# MySens-GWeasySensRS485-002.net
KiCad netlist of a schematic drawn in EAGLE
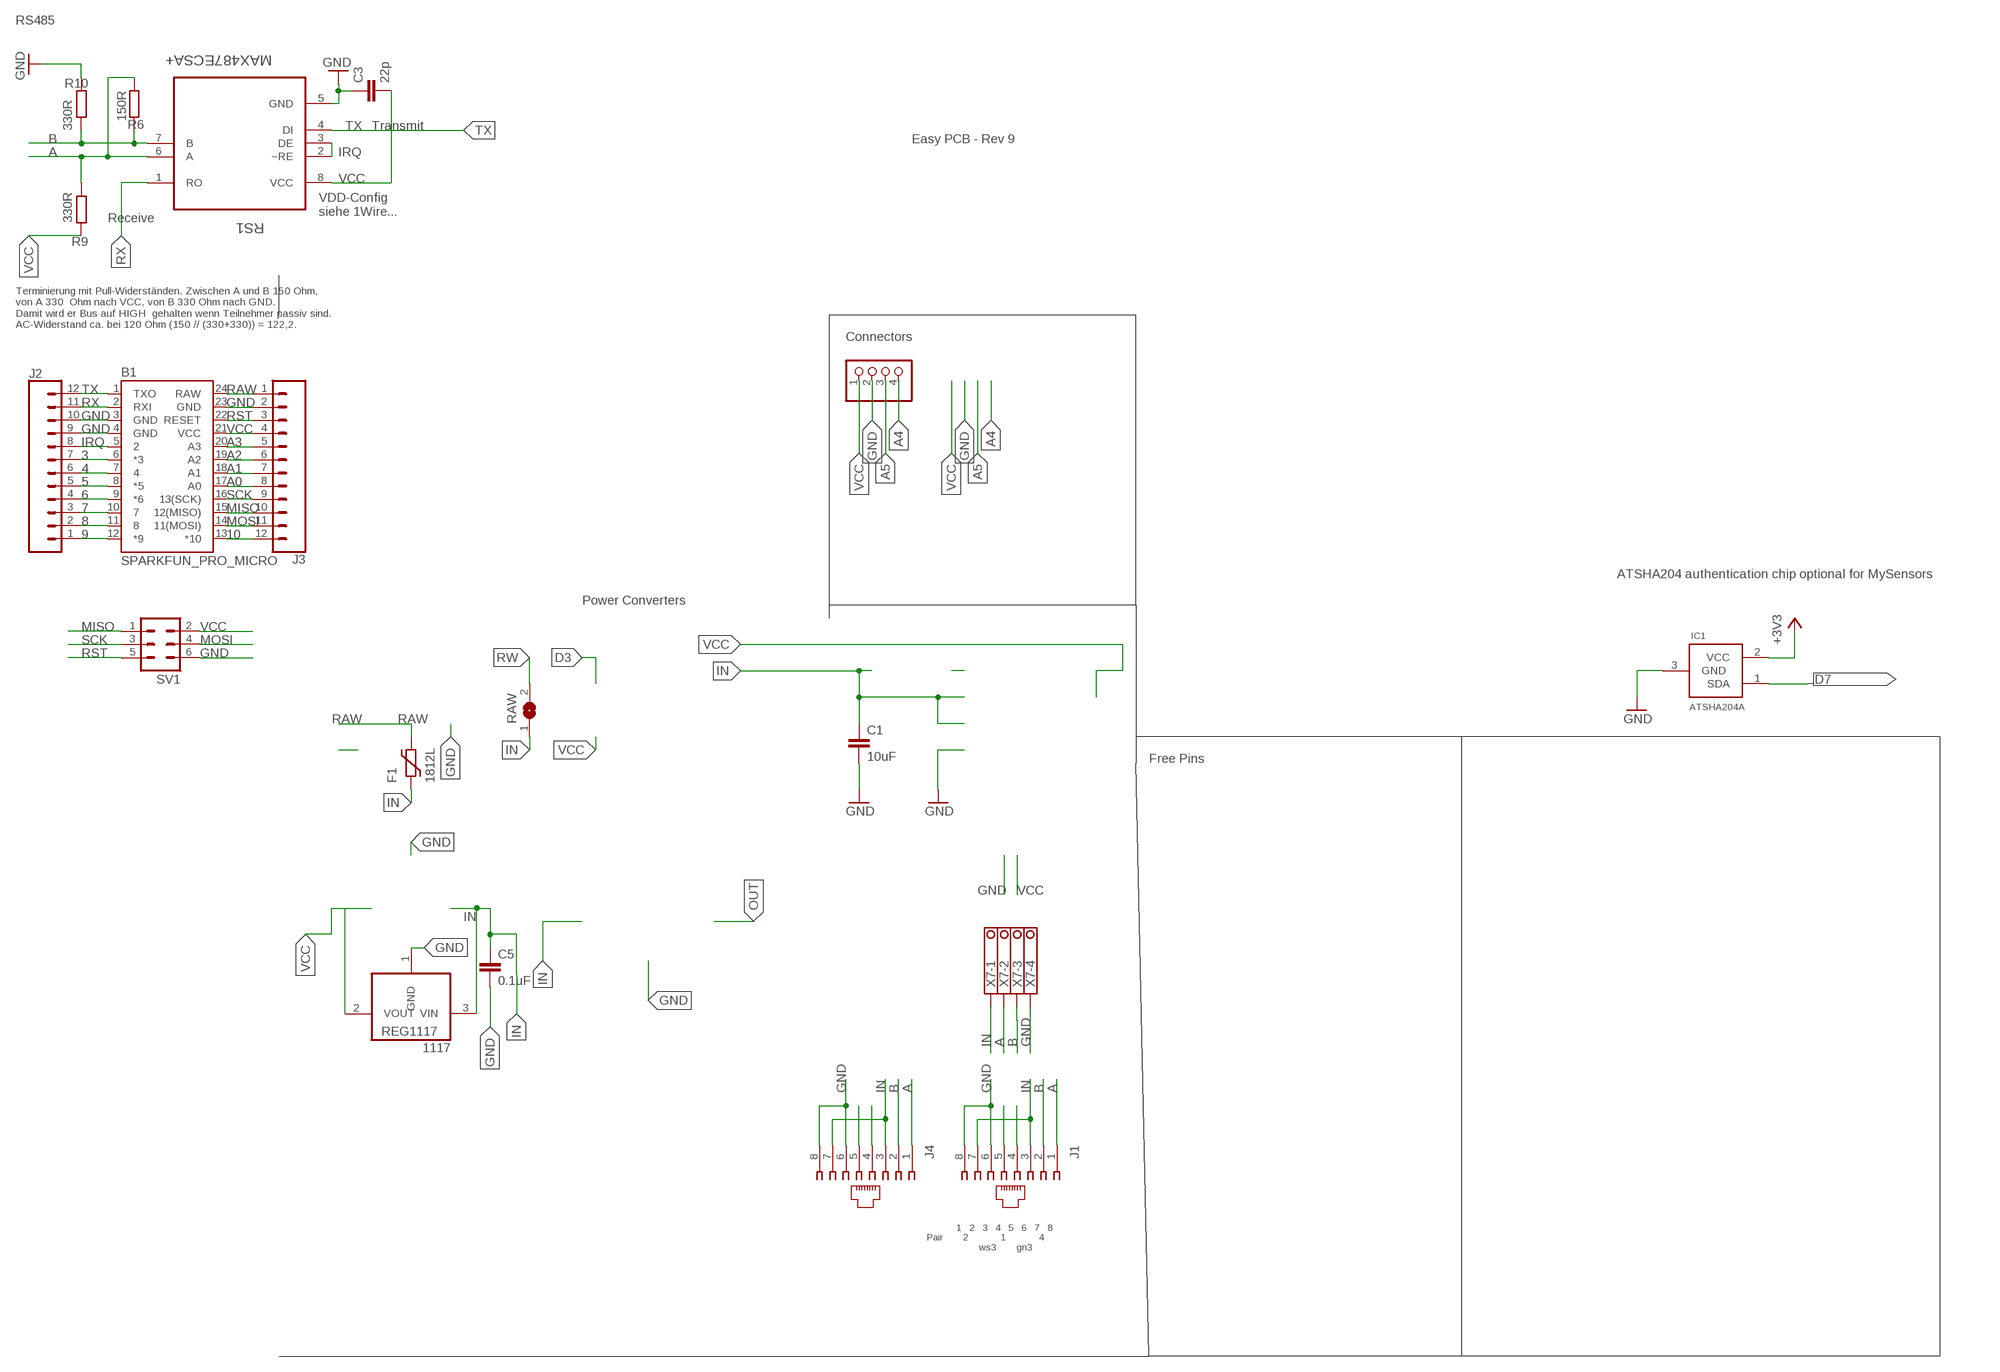
[diagram p0: schematic, sheet 1]

(export (version "E")
  (design (tool "Eeschema 10.0.6"))
  (components
    (comp (ref "1117")
      (value "REG1117")
      (footprint "eagle-import:SOT223")
      (libsource (lib "eagle-import") (part "REG1117"))
    )
    (comp (ref "B1")
      (value "SPARKFUN_PRO_MICRO")
      (footprint "eagle-import:SPARKFUN_PRO_MICRO")
      (libsource (lib "eagle-import") (part "SPARKFUN_PRO_MICRO"))
    )
    (comp (ref "C1")
      (value "10uF")
      (footprint "eagle-import:0805")
      (libsource (lib "eagle-import") (part "CAP0805"))
    )
    (comp (ref "C3")
      (value "22p")
      (footprint "eagle-import:C0805")
      (libsource (lib "eagle-import") (part "C-EUC0805"))
    )
    (comp (ref "C5")
      (value "0.1uF")
      (footprint "eagle-import:C1206")
      (libsource (lib "eagle-import") (part "C-EUC1206"))
    )
    (comp (ref "F1")
      (value "1812L")
      (footprint "eagle-import:1812L")
      (libsource (lib "eagle-import") (part "1812L"))
    )
    (comp (ref "IC1")
      (value "ATSHA204A")
      (footprint "eagle-import:SOT23")
      (libsource (lib "eagle-import") (part "ATSHA204A"))
    )
    (comp (ref "J1")
      (value "215878-2")
      (footprint "eagle-import:215878-2")
      (libsource (lib "eagle-import") (part "215878-2"))
    )
    (comp (ref "J2")
      (value "CONN_12")
      (footprint "eagle-import:1X12")
      (libsource (lib "eagle-import") (part "CONN_12"))
    )
    (comp (ref "J3")
      (value "CONN_12")
      (footprint "eagle-import:1X12")
      (libsource (lib "eagle-import") (part "CONN_12"))
    )
    (comp (ref "J4")
      (value "215878-2")
      (footprint "eagle-import:215878-2")
      (libsource (lib "eagle-import") (part "215878-2"))
    )
    (comp (ref "JP10")
      (value "PINHD-1X04_2.54-S")
      (footprint "eagle-import:1X04-S")
      (libsource (lib "eagle-import") (part "PINHD-1X04_2.54-S"))
    )
    (comp (ref "R6")
      (value "150R")
      (footprint "eagle-import:R0805")
      (libsource (lib "eagle-import") (part "R-EU_R0805"))
    )
    (comp (ref "R9")
      (value "330R")
      (footprint "eagle-import:R0805")
      (libsource (lib "eagle-import") (part "R-EU_R0805"))
    )
    (comp (ref "R10")
      (value "330R")
      (footprint "eagle-import:R0805")
      (libsource (lib "eagle-import") (part "R-EU_R0805"))
    )
    (comp (ref "RAW") (value "SJ") (footprint "eagle-import:SJ") (libsource (lib "eagle-import") (part "SJ")))
    (comp (ref "RS1")
      (value "MAX487ECSA+")
      (footprint "eagle-import:SOIC127P600X175-8N")
      (libsource (lib "eagle-import") (part "MAX487ECSA+"))
    )
    (comp (ref "SV1")
      (value "MA03-2")
      (footprint "eagle-import:MA03-2")
      (libsource (lib "eagle-import") (part "MA03-2"))
    )
    (comp (ref "X7")
      (value "1751264")
      (footprint "eagle-import:1751264")
      (libsource (lib "eagle-import") (part "1751264"))
    )
  )
  (nets
    (net (code "1") (name "+3V3") (class "Default")
      (node (ref "IC1") (pin "2") (pinfunction "VCC_2") (pintype "bidirectional"))
    )
    (net (code "2") (name "/3") (class "Default")
      (node (ref "B1") (pin "6") (pinfunction "*3_6") (pintype "bidirectional"))
      (node (ref "J2") (pin "7") (pinfunction "7_7") (pintype "passive"))
    )
    (net (code "3") (name "/4") (class "Default")
      (node (ref "B1") (pin "7") (pinfunction "4_7") (pintype "bidirectional"))
      (node (ref "J2") (pin "6") (pinfunction "6_6") (pintype "passive"))
    )
    (net (code "4") (name "/5") (class "Default")
      (node (ref "B1") (pin "8") (pinfunction "*5_8") (pintype "bidirectional"))
      (node (ref "J2") (pin "5") (pinfunction "5_5") (pintype "passive"))
    )
    (net (code "5") (name "/6") (class "Default")
      (node (ref "B1") (pin "9") (pinfunction "*6_9") (pintype "bidirectional"))
      (node (ref "J2") (pin "4") (pinfunction "4_4") (pintype "passive"))
    )
    (net (code "6") (name "/7") (class "Default")
      (node (ref "B1") (pin "10") (pinfunction "7_10") (pintype "bidirectional"))
      (node (ref "J2") (pin "3") (pinfunction "3_3") (pintype "passive"))
    )
    (net (code "7") (name "/8") (class "Default")
      (node (ref "B1") (pin "11") (pinfunction "8_11") (pintype "bidirectional"))
      (node (ref "J2") (pin "2") (pinfunction "2_2") (pintype "passive"))
    )
    (net (code "8") (name "/9") (class "Default")
      (node (ref "B1") (pin "12") (pinfunction "*9_12") (pintype "bidirectional"))
      (node (ref "J2") (pin "1") (pinfunction "1_1") (pintype "passive"))
    )
    (net (code "9") (name "/10") (class "Default")
      (node (ref "B1") (pin "13") (pinfunction "*10_13") (pintype "bidirectional"))
      (node (ref "J3") (pin "12") (pinfunction "12_12") (pintype "passive"))
    )
    (net (code "10") (name "/A") (class "Default")
      (node (ref "J1") (pin "1") (pinfunction "1_1") (pintype "passive"))
      (node (ref "J4") (pin "1") (pinfunction "1_1") (pintype "passive"))
      (node (ref "R6") (pin "1") (pinfunction "1_1") (pintype "passive"))
      (node (ref "R9") (pin "2") (pinfunction "2_2") (pintype "passive"))
      (node (ref "RS1") (pin "6") (pinfunction "A_6") (pintype "bidirectional"))
      (node (ref "X7") (pin "2") (pinfunction "K_2") (pintype "passive"))
    )
    (net (code "11") (name "/A0") (class "Default")
      (node (ref "B1") (pin "17") (pinfunction "A0_17") (pintype "bidirectional"))
      (node (ref "J3") (pin "8") (pinfunction "8_8") (pintype "passive"))
    )
    (net (code "12") (name "/A1") (class "Default")
      (node (ref "B1") (pin "18") (pinfunction "A1_18") (pintype "bidirectional"))
      (node (ref "J3") (pin "7") (pinfunction "7_7") (pintype "passive"))
    )
    (net (code "13") (name "/A2") (class "Default")
      (node (ref "B1") (pin "19") (pinfunction "A2_19") (pintype "bidirectional"))
      (node (ref "J3") (pin "6") (pinfunction "6_6") (pintype "passive"))
    )
    (net (code "14") (name "/A3") (class "Default")
      (node (ref "B1") (pin "20") (pinfunction "A3_20") (pintype "bidirectional"))
      (node (ref "J3") (pin "5") (pinfunction "5_5") (pintype "passive"))
    )
    (net (code "15") (name "/B") (class "Default")
      (node (ref "J1") (pin "2") (pinfunction "2_2") (pintype "passive"))
      (node (ref "J4") (pin "2") (pinfunction "2_2") (pintype "passive"))
      (node (ref "R10") (pin "1") (pinfunction "1_1") (pintype "passive"))
      (node (ref "R6") (pin "2") (pinfunction "2_2") (pintype "passive"))
      (node (ref "RS1") (pin "7") (pinfunction "B_7") (pintype "bidirectional"))
      (node (ref "X7") (pin "3") (pinfunction "K_3") (pintype "passive"))
    )
    (net (code "16") (name "/D7") (class "Default")
      (node (ref "IC1") (pin "1") (pinfunction "SDA_1") (pintype "bidirectional"))
    )
    (net (code "17") (name "/IRQ") (class "Default")
      (node (ref "B1") (pin "5") (pinfunction "2_5") (pintype "bidirectional"))
      (node (ref "J2") (pin "8") (pinfunction "8_8") (pintype "passive"))
      (node (ref "RS1") (pin "2") (pinfunction "~{RE}_2") (pintype "input"))
      (node (ref "RS1") (pin "3") (pinfunction "DE_3") (pintype "input"))
    )
    (net (code "18") (name "/MISO") (class "Default")
      (node (ref "B1") (pin "15") (pinfunction "12(MISO)_15") (pintype "bidirectional"))
      (node (ref "J3") (pin "10") (pinfunction "10_10") (pintype "passive"))
      (node (ref "SV1") (pin "1") (pinfunction "1_1") (pintype "passive"))
    )
    (net (code "19") (name "/MOSI") (class "Default")
      (node (ref "B1") (pin "14") (pinfunction "11(MOSI)_14") (pintype "bidirectional"))
      (node (ref "J3") (pin "11") (pinfunction "11_11") (pintype "passive"))
      (node (ref "SV1") (pin "4") (pinfunction "4_4") (pintype "passive"))
    )
    (net (code "20") (name "/RAW") (class "Default")
      (node (ref "B1") (pin "24") (pinfunction "RAW_24") (pintype "power_in"))
      (node (ref "F1") (pin "P$2") (pinfunction "2_P$2") (pintype "passive"))
      (node (ref "J3") (pin "1") (pinfunction "1_1") (pintype "passive"))
    )
    (net (code "21") (name "/RST") (class "Default")
      (node (ref "B1") (pin "22") (pinfunction "RESET_22") (pintype "bidirectional"))
      (node (ref "J3") (pin "3") (pinfunction "3_3") (pintype "passive"))
      (node (ref "SV1") (pin "5") (pinfunction "5_5") (pintype "passive"))
    )
    (net (code "22") (name "/SCK") (class "Default")
      (node (ref "B1") (pin "16") (pinfunction "13(SCK)_16") (pintype "bidirectional"))
      (node (ref "J3") (pin "9") (pinfunction "9_9") (pintype "passive"))
      (node (ref "SV1") (pin "3") (pinfunction "3_3") (pintype "passive"))
    )
    (net (code "23") (name "A4") (class "Default")
      (node (ref "JP10") (pin "4") (pinfunction "4_4") (pintype "passive"))
    )
    (net (code "24") (name "A5") (class "Default")
      (node (ref "JP10") (pin "3") (pinfunction "3_3") (pintype "passive"))
    )
    (net (code "26") (name "GND") (class "Default")
      (node (ref "1117") (pin "1") (pinfunction "GND_1") (pintype "power_in"))
      (node (ref "B1") (pin "23") (pinfunction "GND_23") (pintype "power_in"))
      (node (ref "B1") (pin "3") (pinfunction "GND_3") (pintype "power_in"))
      (node (ref "B1") (pin "4") (pinfunction "GND_4") (pintype "power_in"))
      (node (ref "C1") (pin "2") (pinfunction "2_2") (pintype "passive"))
      (node (ref "C3") (pin "1") (pinfunction "1_1") (pintype "passive"))
      (node (ref "C5") (pin "2") (pinfunction "2_2") (pintype "passive"))
      (node (ref "IC1") (pin "3") (pinfunction "GND_3") (pintype "bidirectional"))
      (node (ref "J1") (pin "6") (pinfunction "6_6") (pintype "passive"))
      (node (ref "J1") (pin "8") (pinfunction "8_8") (pintype "passive"))
      (node (ref "J2") (pin "10") (pinfunction "10_10") (pintype "passive"))
      (node (ref "J2") (pin "9") (pinfunction "9_9") (pintype "passive"))
      (node (ref "J3") (pin "2") (pinfunction "2_2") (pintype "passive"))
      (node (ref "J4") (pin "6") (pinfunction "6_6") (pintype "passive"))
      (node (ref "J4") (pin "8") (pinfunction "8_8") (pintype "passive"))
      (node (ref "JP10") (pin "2") (pinfunction "2_2") (pintype "passive"))
      (node (ref "R10") (pin "2") (pinfunction "2_2") (pintype "passive"))
      (node (ref "RS1") (pin "5") (pinfunction "GND_5") (pintype "passive"))
      (node (ref "SV1") (pin "6") (pinfunction "6_6") (pintype "passive"))
      (node (ref "X7") (pin "4") (pinfunction "K_4") (pintype "passive"))
    )
    (net (code "27") (name "IN") (class "Default")
      (node (ref "1117") (pin "3") (pinfunction "VIN_3") (pintype "input"))
      (node (ref "C1") (pin "1") (pinfunction "1_1") (pintype "passive"))
      (node (ref "C5") (pin "1") (pinfunction "1_1") (pintype "passive"))
      (node (ref "F1") (pin "P$1") (pinfunction "1_P$1") (pintype "passive"))
      (node (ref "J1") (pin "3") (pinfunction "3_3") (pintype "passive"))
      (node (ref "J1") (pin "7") (pinfunction "7_7") (pintype "passive"))
      (node (ref "J4") (pin "3") (pinfunction "3_3") (pintype "passive"))
      (node (ref "J4") (pin "7") (pinfunction "7_7") (pintype "passive"))
      (node (ref "RAW") (pin "1") (pinfunction "1_1") (pintype "passive"))
      (node (ref "X7") (pin "1") (pinfunction "K_1") (pintype "passive"))
    )
    (net (code "29") (name "RW") (class "Default")
      (node (ref "RAW") (pin "2") (pinfunction "2_2") (pintype "passive"))
    )
    (net (code "30") (name "RX") (class "Default")
      (node (ref "B1") (pin "2") (pinfunction "RXI_2") (pintype "bidirectional"))
      (node (ref "J2") (pin "11") (pinfunction "11_11") (pintype "passive"))
      (node (ref "RS1") (pin "1") (pinfunction "RO_1") (pintype "output"))
    )
    (net (code "31") (name "TX") (class "Default")
      (node (ref "B1") (pin "1") (pinfunction "TXO_1") (pintype "bidirectional"))
      (node (ref "J2") (pin "12") (pinfunction "12_12") (pintype "passive"))
      (node (ref "RS1") (pin "4") (pinfunction "DI_4") (pintype "input"))
    )
    (net (code "32") (name "VCC") (class "Default")
      (node (ref "1117") (pin "2") (pinfunction "VOUT_2") (pintype "output"))
      (node (ref "B1") (pin "21") (pinfunction "VCC_21") (pintype "power_in"))
      (node (ref "C3") (pin "2") (pinfunction "2_2") (pintype "passive"))
      (node (ref "J3") (pin "4") (pinfunction "4_4") (pintype "passive"))
      (node (ref "JP10") (pin "1") (pinfunction "1_1") (pintype "passive"))
      (node (ref "R9") (pin "1") (pinfunction "1_1") (pintype "passive"))
      (node (ref "RS1") (pin "8") (pinfunction "VCC_8") (pintype "power_in"))
      (node (ref "SV1") (pin "2") (pinfunction "2_2") (pintype "passive"))
    )
    (net (code "33") (name "unconnected-(J1-Pad4)") (class "Default")
      (node (ref "J1") (pin "4") (pinfunction "4_4") (pintype "passive"))
    )
    (net (code "34") (name "unconnected-(J1-Pad5)") (class "Default")
      (node (ref "J1") (pin "5") (pinfunction "5_5") (pintype "passive"))
    )
    (net (code "35") (name "unconnected-(J4-Pad4)") (class "Default")
      (node (ref "J4") (pin "4") (pinfunction "4_4") (pintype "passive"))
    )
    (net (code "36") (name "unconnected-(J4-Pad5)") (class "Default")
      (node (ref "J4") (pin "5") (pinfunction "5_5") (pintype "passive"))
    )
  )
)
